# workingflasher.net
KiCad netlist of a schematic drawn in EAGLE
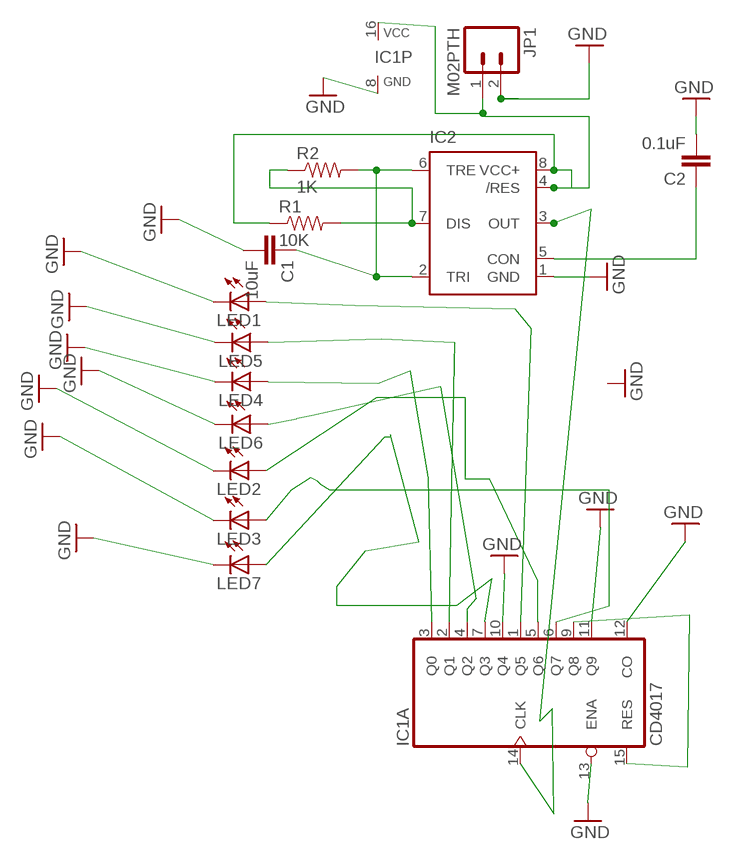
[diagram p0: schematic, sheet 1]

(export (version "E")
  (design (tool "Eeschema 10.0.6"))
  (components
    (comp (ref "C1")
      (value "10uF")
      (footprint "eagle-import:1210")
      (libsource (lib "eagle-import") (part "10UF50V20%(1210)"))
    )
    (comp (ref "C2")
      (value "0.1uF")
      (footprint "eagle-import:0603-CAP")
      (libsource (lib "eagle-import") (part "0.1UF-25V(+80/-20%)(0603)"))
    )
    (comp (ref "IC1")
      (value "CD4017")
      (footprint "eagle-import:DIL16")
      (libsource (lib "eagle-import") (part "CD4017"))
    )
    (comp (ref "IC2")
      (value "NE555D")
      (footprint "eagle-import:SO08")
      (libsource (lib "eagle-import") (part "NE555D"))
    )
    (comp (ref "JP1")
      (value "M02PTH")
      (footprint "eagle-import:1X02")
      (libsource (lib "eagle-import") (part "M02PTH"))
    )
    (comp (ref "LED1")
      (value "LED1206")
      (footprint "eagle-import:LED-1206")
      (libsource (lib "eagle-import") (part "LED1206"))
    )
    (comp (ref "LED2")
      (value "LED1206")
      (footprint "eagle-import:LED-1206")
      (libsource (lib "eagle-import") (part "LED1206"))
    )
    (comp (ref "LED3")
      (value "LED1206")
      (footprint "eagle-import:LED-1206")
      (libsource (lib "eagle-import") (part "LED1206"))
    )
    (comp (ref "LED4")
      (value "LED1206")
      (footprint "eagle-import:LED-1206")
      (libsource (lib "eagle-import") (part "LED1206"))
    )
    (comp (ref "LED5")
      (value "LED1206")
      (footprint "eagle-import:LED-1206")
      (libsource (lib "eagle-import") (part "LED1206"))
    )
    (comp (ref "LED6")
      (value "LED1206")
      (footprint "eagle-import:LED-1206")
      (libsource (lib "eagle-import") (part "LED1206"))
    )
    (comp (ref "LED7")
      (value "LED1206")
      (footprint "eagle-import:LED-1206")
      (libsource (lib "eagle-import") (part "LED1206"))
    )
    (comp (ref "R1")
      (value "10K")
      (footprint "eagle-import:0603")
      (libsource (lib "eagle-import") (part "0OHM1/10W5%(0603)"))
    )
    (comp (ref "R2")
      (value "1K")
      (footprint "eagle-import:0603")
      (libsource (lib "eagle-import") (part "0OHM1/10W5%(0603)"))
    )
  )
  (nets
    (net (code "1") (name "GND") (class "Default")
      (node (ref "C1") (pin "2") (pinfunction "2_2") (pintype "passive"))
      (node (ref "C2") (pin "2") (pinfunction "2_2") (pintype "passive"))
      (node (ref "IC1") (pin "10") (pinfunction "Q4_10") (pintype "output"))
      (node (ref "IC1") (pin "11") (pinfunction "Q9_11") (pintype "output"))
      (node (ref "IC1") (pin "12") (pinfunction "CO_12") (pintype "output"))
      (node (ref "IC1") (pin "13") (pinfunction "ENA_13") (pintype "input"))
      (node (ref "IC1") (pin "8") (pinfunction "GND_8") (pintype "power_in"))
      (node (ref "IC2") (pin "1") (pinfunction "GND_1") (pintype "power_in"))
      (node (ref "JP1") (pin "2") (pinfunction "2_2") (pintype "passive"))
      (node (ref "LED1") (pin "C") (pinfunction "C_C") (pintype "passive"))
      (node (ref "LED2") (pin "C") (pinfunction "C_C") (pintype "passive"))
      (node (ref "LED3") (pin "C") (pinfunction "C_C") (pintype "passive"))
      (node (ref "LED4") (pin "C") (pinfunction "C_C") (pintype "passive"))
      (node (ref "LED5") (pin "C") (pinfunction "C_C") (pintype "passive"))
      (node (ref "LED6") (pin "C") (pinfunction "C_C") (pintype "passive"))
      (node (ref "LED7") (pin "C") (pinfunction "C_C") (pintype "passive"))
    )
    (net (code "2") (name "Net-(IC1A-CLK)") (class "Default")
      (node (ref "IC1") (pin "14") (pinfunction "CLK_14") (pintype "input"))
      (node (ref "IC2") (pin "3") (pinfunction "OUT_3") (pintype "output"))
    )
    (net (code "3") (name "Net-(IC1A-Q0)") (class "Default")
      (node (ref "IC1") (pin "3") (pinfunction "Q0_3") (pintype "output"))
      (node (ref "LED4") (pin "A") (pinfunction "A_A") (pintype "passive"))
    )
    (net (code "4") (name "Net-(IC1A-Q1)") (class "Default")
      (node (ref "IC1") (pin "2") (pinfunction "Q1_2") (pintype "output"))
      (node (ref "LED5") (pin "A") (pinfunction "A_A") (pintype "passive"))
    )
    (net (code "5") (name "Net-(IC1A-Q2)") (class "Default")
      (node (ref "IC1") (pin "4") (pinfunction "Q2_4") (pintype "output"))
      (node (ref "LED6") (pin "A") (pinfunction "A_A") (pintype "passive"))
    )
    (net (code "6") (name "Net-(IC1A-Q3)") (class "Default")
      (node (ref "IC1") (pin "7") (pinfunction "Q3_7") (pintype "output"))
      (node (ref "LED7") (pin "A") (pinfunction "A_A") (pintype "passive"))
    )
    (net (code "7") (name "Net-(IC1A-Q5)") (class "Default")
      (node (ref "IC1") (pin "1") (pinfunction "Q5_1") (pintype "output"))
      (node (ref "LED1") (pin "A") (pinfunction "A_A") (pintype "passive"))
    )
    (net (code "8") (name "Net-(IC1A-Q6)") (class "Default")
      (node (ref "IC1") (pin "5") (pinfunction "Q6_5") (pintype "output"))
      (node (ref "LED2") (pin "A") (pinfunction "A_A") (pintype "passive"))
    )
    (net (code "9") (name "Net-(IC1A-Q7)") (class "Default")
      (node (ref "IC1") (pin "6") (pinfunction "Q7_6") (pintype "output"))
      (node (ref "LED3") (pin "A") (pinfunction "A_A") (pintype "passive"))
    )
    (net (code "10") (name "Net-(IC1A-Q8)") (class "Default")
      (node (ref "IC1") (pin "15") (pinfunction "RES_15") (pintype "input"))
      (node (ref "IC1") (pin "9") (pinfunction "Q8_9") (pintype "output"))
    )
    (net (code "11") (name "Net-(IC1B-VCC)") (class "Default")
      (node (ref "IC1") (pin "16") (pinfunction "VCC_16") (pintype "power_in"))
      (node (ref "IC2") (pin "4") (pinfunction "/RES_4") (pintype "input"))
      (node (ref "IC2") (pin "8") (pinfunction "VCC+_8") (pintype "power_in"))
      (node (ref "JP1") (pin "1") (pinfunction "1_1") (pintype "passive"))
      (node (ref "R1") (pin "1") (pinfunction "1_1") (pintype "passive"))
    )
    (net (code "12") (name "Net-(IC2-CON)") (class "Default")
      (node (ref "C2") (pin "1") (pinfunction "1_1") (pintype "passive"))
      (node (ref "IC2") (pin "5") (pinfunction "CON_5") (pintype "input"))
    )
    (net (code "13") (name "Net-(IC2-DIS)") (class "Default")
      (node (ref "IC2") (pin "7") (pinfunction "DIS_7") (pintype "input"))
      (node (ref "R1") (pin "2") (pinfunction "2_2") (pintype "passive"))
      (node (ref "R2") (pin "1") (pinfunction "1_1") (pintype "passive"))
    )
    (net (code "14") (name "Net-(IC2-TRE)") (class "Default")
      (node (ref "C1") (pin "1") (pinfunction "1_1") (pintype "passive"))
      (node (ref "IC2") (pin "2") (pinfunction "TRI_2") (pintype "input"))
      (node (ref "IC2") (pin "6") (pinfunction "TRE_6") (pintype "input"))
      (node (ref "R2") (pin "2") (pinfunction "2_2") (pintype "passive"))
    )
  )
)
